# FSI6CAN.net
KiCad netlist of a schematic drawn in EAGLE
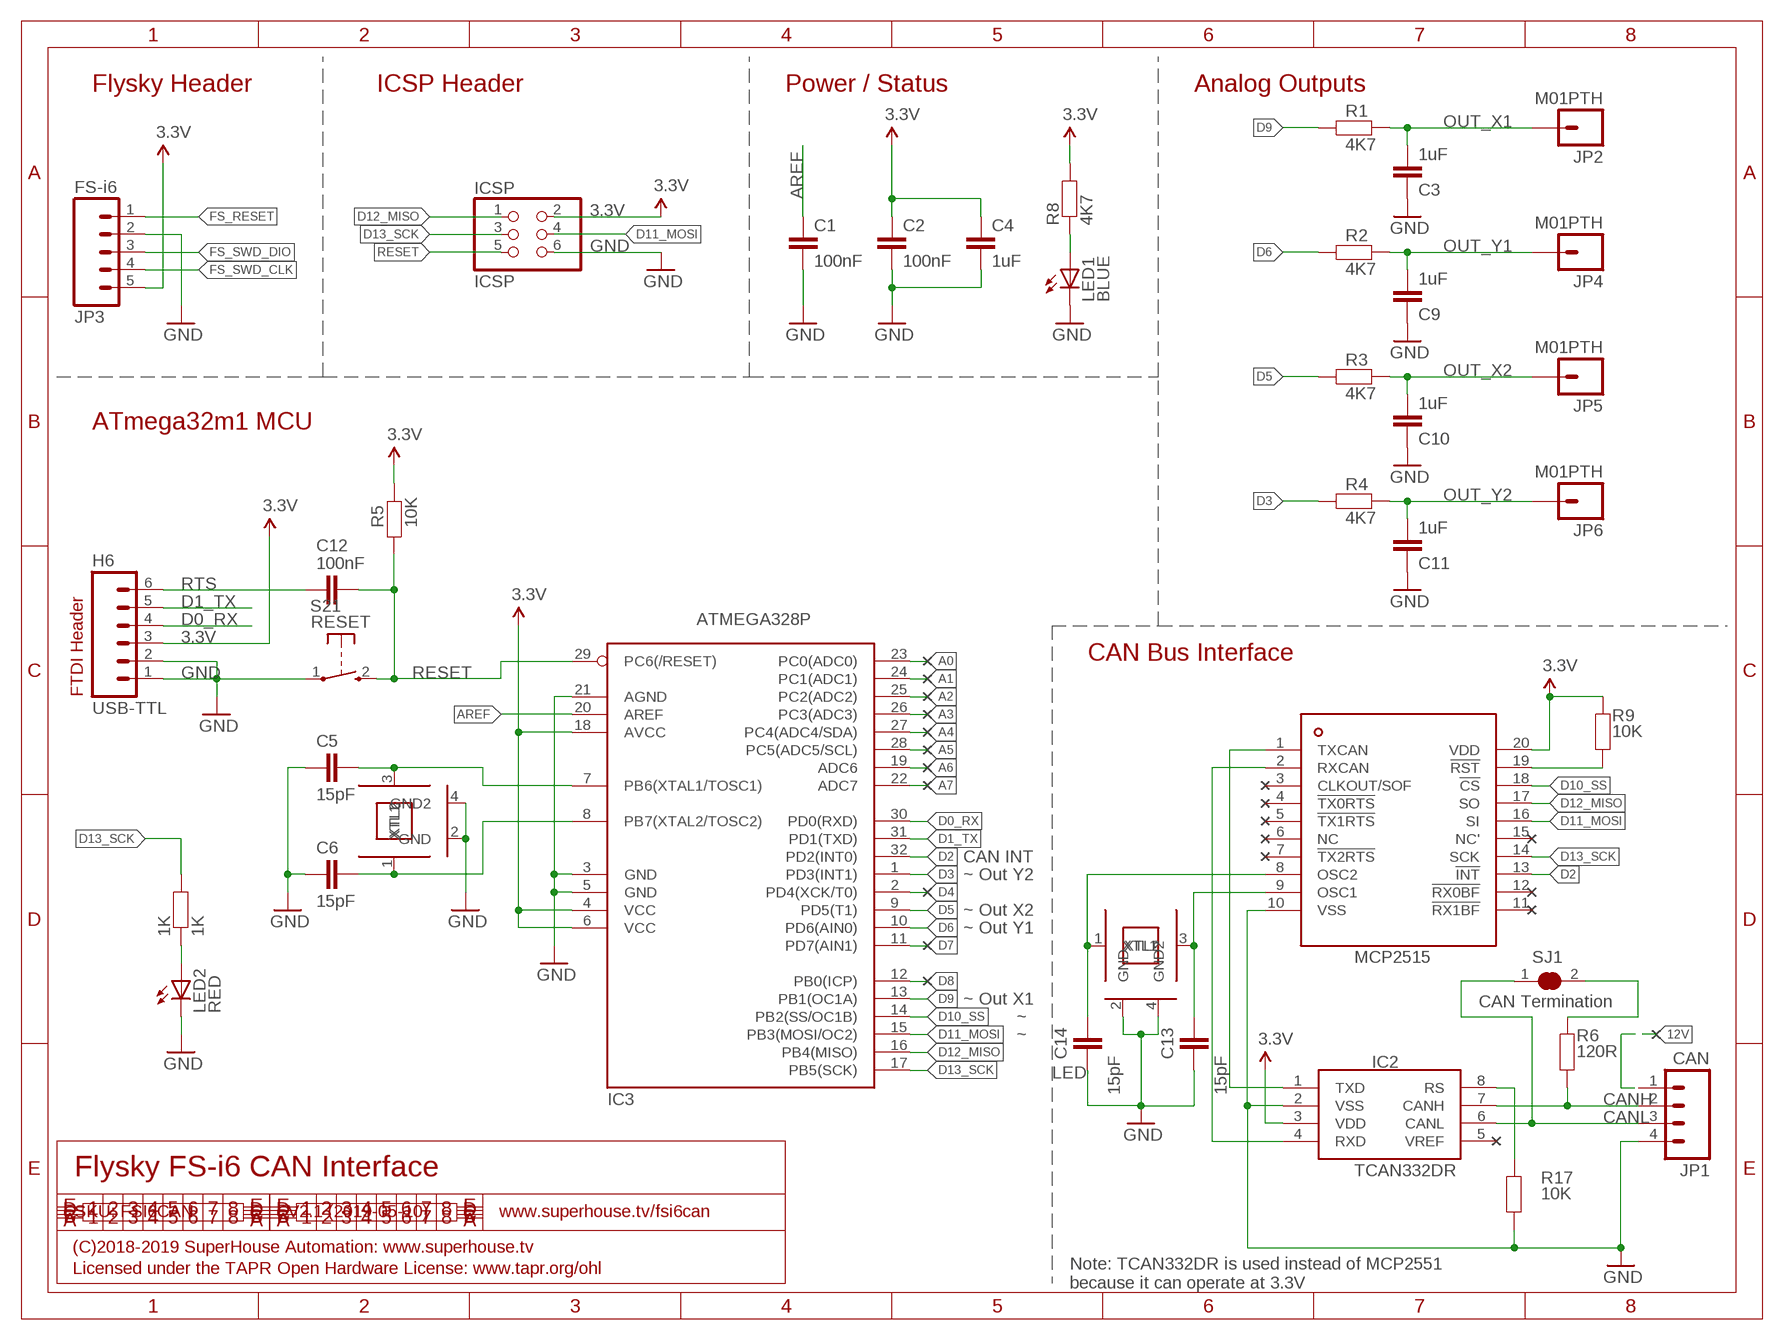
[diagram p0: schematic, sheet 1]

(export (version "E")
  (design (tool "Eeschema 10.0.6"))
  (components
    (comp (ref "1K")
      (value "1K")
      (footprint "eagle-import:R0603")
      (libsource (lib "eagle-import") (part "RESISTOR0603"))
    )
    (comp (ref "C1")
      (value "100nF")
      (footprint "eagle-import:C0603")
      (libsource (lib "eagle-import") (part "CAP0603"))
    )
    (comp (ref "C2")
      (value "100nF")
      (footprint "eagle-import:0603")
      (libsource (lib "eagle-import") (part "freetronics-master-v1.1_CAP0603"))
    )
    (comp (ref "C3")
      (value "1uF")
      (footprint "eagle-import:C0603")
      (libsource (lib "eagle-import") (part "CAP0603"))
    )
    (comp (ref "C4")
      (value "1uF")
      (footprint "eagle-import:0603")
      (libsource (lib "eagle-import") (part "freetronics-master-v1.1_CAP0603"))
    )
    (comp (ref "C5")
      (value "15pF")
      (footprint "eagle-import:C0603")
      (libsource (lib "eagle-import") (part "CAP0603"))
    )
    (comp (ref "C6")
      (value "15pF")
      (footprint "eagle-import:C0603")
      (libsource (lib "eagle-import") (part "CAP0603"))
    )
    (comp (ref "C9")
      (value "1uF")
      (footprint "eagle-import:C0603")
      (libsource (lib "eagle-import") (part "CAP0603"))
    )
    (comp (ref "C10")
      (value "1uF")
      (footprint "eagle-import:C0603")
      (libsource (lib "eagle-import") (part "CAP0603"))
    )
    (comp (ref "C11")
      (value "1uF")
      (footprint "eagle-import:C0603")
      (libsource (lib "eagle-import") (part "CAP0603"))
    )
    (comp (ref "C12")
      (value "100nF")
      (footprint "eagle-import:0603")
      (libsource (lib "eagle-import") (part "freetronics-master-v1.1_CAP0603"))
    )
    (comp (ref "C13")
      (value "15pF")
      (footprint "eagle-import:C0603")
      (libsource (lib "eagle-import") (part "CAP0603"))
    )
    (comp (ref "C14")
      (value "15pF")
      (footprint "eagle-import:C0603")
      (libsource (lib "eagle-import") (part "CAP0603"))
    )
    (comp (ref "H6")
      (value "USB-TTL")
      (footprint "eagle-import:1X06")
      (libsource (lib "eagle-import") (part "M06SIP"))
    )
    (comp (ref "IC2")
      (value "TCAN332DR")
      (footprint "eagle-import:SO08")
      (libsource (lib "eagle-import") (part "MCP2551"))
    )
    (comp (ref "IC3")
      (value "ATMEGA328P")
      (footprint "eagle-import:TQFP32-08")
      (libsource (lib "eagle-import") (part "AVR-MEGA8-AI"))
    )
    (comp (ref "IC4")
      (value "MCP2515")
      (footprint "eagle-import:TSSOP20")
      (libsource (lib "eagle-import") (part "MCP2515"))
    )
    (comp (ref "ICSP")
      (value "ICSP")
      (footprint "eagle-import:2X03")
      (libsource (lib "eagle-import") (part "PINHD-2X3"))
    )
    (comp (ref "JP1")
      (value "CAN")
      (footprint "eagle-import:1X04")
      (libsource (lib "eagle-import") (part "M04PTH"))
    )
    (comp (ref "JP2")
      (value "M01PTH")
      (footprint "eagle-import:1X01")
      (libsource (lib "eagle-import") (part "M01PTH"))
    )
    (comp (ref "JP3")
      (value "FS-i6")
      (footprint "eagle-import:1X05")
      (libsource (lib "eagle-import") (part "M05PTH"))
    )
    (comp (ref "JP4")
      (value "M01PTH")
      (footprint "eagle-import:1X01")
      (libsource (lib "eagle-import") (part "M01PTH"))
    )
    (comp (ref "JP5")
      (value "M01PTH")
      (footprint "eagle-import:1X01")
      (libsource (lib "eagle-import") (part "M01PTH"))
    )
    (comp (ref "JP6")
      (value "M01PTH")
      (footprint "eagle-import:1X01")
      (libsource (lib "eagle-import") (part "M01PTH"))
    )
    (comp (ref "LED1")
      (value "BLUE")
      (footprint "eagle-import:LED-0603")
      (libsource (lib "eagle-import") (part "LED0603"))
    )
    (comp (ref "LED2")
      (value "RED")
      (footprint "eagle-import:LED-0603")
      (libsource (lib "eagle-import") (part "LED0603"))
    )
    (comp (ref "R1")
      (value "4K7")
      (footprint "eagle-import:R0603")
      (libsource (lib "eagle-import") (part "RESISTOR0603"))
    )
    (comp (ref "R2")
      (value "4K7")
      (footprint "eagle-import:R0603")
      (libsource (lib "eagle-import") (part "RESISTOR0603"))
    )
    (comp (ref "R3")
      (value "4K7")
      (footprint "eagle-import:R0603")
      (libsource (lib "eagle-import") (part "RESISTOR0603"))
    )
    (comp (ref "R4")
      (value "4K7")
      (footprint "eagle-import:R0603")
      (libsource (lib "eagle-import") (part "RESISTOR0603"))
    )
    (comp (ref "R5")
      (value "10K")
      (footprint "eagle-import:0603")
      (libsource (lib "eagle-import") (part "freetronics-master-v1.1_RESISTOR0603"))
    )
    (comp (ref "R6")
      (value "120R")
      (footprint "eagle-import:0603")
      (libsource (lib "eagle-import") (part "freetronics-master-v1.1_RESISTOR0603"))
    )
    (comp (ref "R8")
      (value "4K7")
      (footprint "eagle-import:0603")
      (libsource (lib "eagle-import") (part "freetronics-jon_RESISTOR0603"))
    )
    (comp (ref "R9")
      (value "10K")
      (footprint "eagle-import:R0603")
      (libsource (lib "eagle-import") (part "RESISTOR0603"))
    )
    (comp (ref "R17")
      (value "10K")
      (footprint "eagle-import:R0603")
      (libsource (lib "eagle-import") (part "RESISTOR0603"))
    )
    (comp (ref "S21")
      (value "RESET")
      (footprint "eagle-import:TACTILE_SMT_3X4X2")
      (libsource (lib "eagle-import") (part "TAC_SWITCH_2PINSMT"))
    )
    (comp (ref "SJ1")
      (value "CAN Termination")
      (footprint "eagle-import:SJC")
      (libsource (lib "eagle-import") (part "SJCN"))
    )
    (comp (ref "XTL1")
      (value "8MHz")
      (footprint "eagle-import:CRYSTAL-SMD-3X2")
      (libsource (lib "eagle-import") (part "CRYSTAL-GND3X2"))
    )
    (comp (ref "XTL3")
      (value "16MHz")
      (footprint "eagle-import:CRYSTAL-SMD-3X2")
      (libsource (lib "eagle-import") (part "CRYSTAL-GND3X2"))
    )
  )
  (nets
    (net (code "1") (name "/CANH") (class "Default")
      (node (ref "IC2") (pin "7") (pinfunction "CANH_7") (pintype "bidirectional"))
      (node (ref "JP1") (pin "2") (pinfunction "2_2") (pintype "passive"))
      (node (ref "R6") (pin "1") (pinfunction "1_1") (pintype "passive"))
    )
    (net (code "2") (name "/CANL") (class "Default")
      (node (ref "IC2") (pin "6") (pinfunction "CANL_6") (pintype "bidirectional"))
      (node (ref "JP1") (pin "3") (pinfunction "3_3") (pintype "passive"))
      (node (ref "SJ1") (pin "1") (pinfunction "1_1") (pintype "passive"))
    )
    (net (code "3") (name "/OUT_X1") (class "Default")
      (node (ref "C3") (pin "1") (pinfunction "1_1") (pintype "passive"))
      (node (ref "JP2") (pin "1") (pinfunction "1_1") (pintype "passive"))
      (node (ref "R1") (pin "2") (pinfunction "2_2") (pintype "passive"))
    )
    (net (code "4") (name "/OUT_X2") (class "Default")
      (node (ref "C10") (pin "1") (pinfunction "1_1") (pintype "passive"))
      (node (ref "JP5") (pin "1") (pinfunction "1_1") (pintype "passive"))
      (node (ref "R3") (pin "2") (pinfunction "2_2") (pintype "passive"))
    )
    (net (code "5") (name "/OUT_Y1") (class "Default")
      (node (ref "C9") (pin "1") (pinfunction "1_1") (pintype "passive"))
      (node (ref "JP4") (pin "1") (pinfunction "1_1") (pintype "passive"))
      (node (ref "R2") (pin "2") (pinfunction "2_2") (pintype "passive"))
    )
    (net (code "6") (name "/OUT_Y2") (class "Default")
      (node (ref "C11") (pin "1") (pinfunction "1_1") (pintype "passive"))
      (node (ref "JP6") (pin "1") (pinfunction "1_1") (pintype "passive"))
      (node (ref "R4") (pin "2") (pinfunction "2_2") (pintype "passive"))
    )
    (net (code "7") (name "/RTS") (class "Default")
      (node (ref "C12") (pin "1") (pinfunction "1_1") (pintype "passive"))
      (node (ref "H6") (pin "6") (pinfunction "6_6") (pintype "passive"))
    )
    (net (code "8") (name "3.3V") (class "Default")
      (node (ref "C2") (pin "1") (pinfunction "1_1") (pintype "passive"))
      (node (ref "C4") (pin "1") (pinfunction "1_1") (pintype "passive"))
      (node (ref "H6") (pin "3") (pinfunction "3_3") (pintype "passive"))
      (node (ref "IC2") (pin "3") (pinfunction "VDD_3") (pintype "bidirectional"))
      (node (ref "IC3") (pin "18") (pinfunction "AVCC_18") (pintype "bidirectional"))
      (node (ref "IC3") (pin "4") (pinfunction "VCC_4") (pintype "bidirectional"))
      (node (ref "IC3") (pin "6") (pinfunction "VCC_6") (pintype "bidirectional"))
      (node (ref "IC4") (pin "20") (pinfunction "VDD_20") (pintype "bidirectional"))
      (node (ref "ICSP") (pin "2") (pinfunction "2_2") (pintype "passive"))
      (node (ref "JP3") (pin "5") (pinfunction "5_5") (pintype "passive"))
      (node (ref "R5") (pin "1") (pinfunction "1_1") (pintype "passive"))
      (node (ref "R8") (pin "2") (pinfunction "2_2") (pintype "passive"))
      (node (ref "R9") (pin "2") (pinfunction "2_2") (pintype "passive"))
    )
    (net (code "9") (name "12V") (class "Default")
      (node (ref "JP1") (pin "1") (pinfunction "1_1") (pintype "passive"))
    )
    (net (code "10") (name "A0") (class "Default")
      (node (ref "IC3") (pin "23") (pinfunction "PC0(ADC0)_23") (pintype "bidirectional"))
    )
    (net (code "11") (name "A1") (class "Default")
      (node (ref "IC3") (pin "24") (pinfunction "PC1(ADC1)_24") (pintype "bidirectional"))
    )
    (net (code "12") (name "A2") (class "Default")
      (node (ref "IC3") (pin "25") (pinfunction "PC2(ADC2)_25") (pintype "bidirectional"))
    )
    (net (code "13") (name "A3") (class "Default")
      (node (ref "IC3") (pin "26") (pinfunction "PC3(ADC3)_26") (pintype "bidirectional"))
    )
    (net (code "14") (name "A4") (class "Default")
      (node (ref "IC3") (pin "27") (pinfunction "PC4(ADC4/SDA)_27") (pintype "bidirectional"))
    )
    (net (code "15") (name "A5") (class "Default")
      (node (ref "IC3") (pin "28") (pinfunction "PC5(ADC5/SCL)_28") (pintype "bidirectional"))
    )
    (net (code "16") (name "A6") (class "Default")
      (node (ref "IC3") (pin "19") (pinfunction "ADC6_19") (pintype "bidirectional"))
    )
    (net (code "17") (name "A7") (class "Default")
      (node (ref "IC3") (pin "22") (pinfunction "ADC7_22") (pintype "bidirectional"))
    )
    (net (code "18") (name "AREF") (class "Default")
      (node (ref "C1") (pin "1") (pinfunction "1_1") (pintype "passive"))
      (node (ref "IC3") (pin "20") (pinfunction "AREF_20") (pintype "bidirectional"))
    )
    (net (code "19") (name "D0_RX") (class "Default")
      (node (ref "H6") (pin "4") (pinfunction "4_4") (pintype "passive"))
      (node (ref "IC3") (pin "30") (pinfunction "PD0(RXD)_30") (pintype "bidirectional"))
    )
    (net (code "20") (name "D1_TX") (class "Default")
      (node (ref "H6") (pin "5") (pinfunction "5_5") (pintype "passive"))
      (node (ref "IC3") (pin "31") (pinfunction "PD1(TXD)_31") (pintype "bidirectional"))
    )
    (net (code "21") (name "D2") (class "Default")
      (node (ref "IC3") (pin "32") (pinfunction "PD2(INT0)_32") (pintype "bidirectional"))
      (node (ref "IC4") (pin "13") (pinfunction "~{INT}_13") (pintype "bidirectional"))
    )
    (net (code "22") (name "D3") (class "Default")
      (node (ref "IC3") (pin "1") (pinfunction "PD3(INT1)_1") (pintype "bidirectional"))
      (node (ref "R4") (pin "1") (pinfunction "1_1") (pintype "passive"))
    )
    (net (code "23") (name "D4") (class "Default")
      (node (ref "IC3") (pin "2") (pinfunction "PD4(XCK/T0)_2") (pintype "bidirectional"))
    )
    (net (code "24") (name "D5") (class "Default")
      (node (ref "IC3") (pin "9") (pinfunction "PD5(T1)_9") (pintype "bidirectional"))
      (node (ref "R3") (pin "1") (pinfunction "1_1") (pintype "passive"))
    )
    (net (code "25") (name "D6") (class "Default")
      (node (ref "IC3") (pin "10") (pinfunction "PD6(AIN0)_10") (pintype "bidirectional"))
      (node (ref "R2") (pin "1") (pinfunction "1_1") (pintype "passive"))
    )
    (net (code "26") (name "D7") (class "Default")
      (node (ref "IC3") (pin "11") (pinfunction "PD7(AIN1)_11") (pintype "bidirectional"))
    )
    (net (code "27") (name "D8") (class "Default")
      (node (ref "IC3") (pin "12") (pinfunction "PB0(ICP)_12") (pintype "bidirectional"))
    )
    (net (code "28") (name "D9") (class "Default")
      (node (ref "IC3") (pin "13") (pinfunction "PB1(OC1A)_13") (pintype "bidirectional"))
      (node (ref "R1") (pin "1") (pinfunction "1_1") (pintype "passive"))
    )
    (net (code "29") (name "D10_SS") (class "Default")
      (node (ref "IC3") (pin "14") (pinfunction "PB2(SS/OC1B)_14") (pintype "bidirectional"))
      (node (ref "IC4") (pin "18") (pinfunction "~{CS}_18") (pintype "bidirectional"))
    )
    (net (code "30") (name "D11_MOSI") (class "Default")
      (node (ref "IC3") (pin "15") (pinfunction "PB3(MOSI/OC2)_15") (pintype "bidirectional"))
      (node (ref "IC4") (pin "16") (pinfunction "SI_16") (pintype "bidirectional"))
      (node (ref "ICSP") (pin "4") (pinfunction "4_4") (pintype "passive"))
    )
    (net (code "31") (name "D12_MISO") (class "Default")
      (node (ref "IC3") (pin "16") (pinfunction "PB4(MISO)_16") (pintype "bidirectional"))
      (node (ref "IC4") (pin "17") (pinfunction "SO_17") (pintype "bidirectional"))
      (node (ref "ICSP") (pin "1") (pinfunction "1_1") (pintype "passive"))
    )
    (net (code "32") (name "D13_SCK") (class "Default")
      (node (ref "1K") (pin "2") (pinfunction "2_2") (pintype "passive"))
      (node (ref "IC3") (pin "17") (pinfunction "PB5(SCK)_17") (pintype "bidirectional"))
      (node (ref "IC4") (pin "14") (pinfunction "SCK_14") (pintype "bidirectional"))
      (node (ref "ICSP") (pin "3") (pinfunction "3_3") (pintype "passive"))
    )
    (net (code "33") (name "FS_RESET") (class "Default")
      (node (ref "JP3") (pin "1") (pinfunction "1_1") (pintype "passive"))
    )
    (net (code "34") (name "FS_SWD_CLK") (class "Default")
      (node (ref "JP3") (pin "4") (pinfunction "4_4") (pintype "passive"))
    )
    (net (code "35") (name "FS_SWD_DIO") (class "Default")
      (node (ref "JP3") (pin "3") (pinfunction "3_3") (pintype "passive"))
    )
    (net (code "36") (name "GND") (class "Default")
      (node (ref "C1") (pin "2") (pinfunction "2_2") (pintype "passive"))
      (node (ref "C10") (pin "2") (pinfunction "2_2") (pintype "passive"))
      (node (ref "C11") (pin "2") (pinfunction "2_2") (pintype "passive"))
      (node (ref "C13") (pin "1") (pinfunction "1_1") (pintype "passive"))
      (node (ref "C14") (pin "1") (pinfunction "1_1") (pintype "passive"))
      (node (ref "C2") (pin "2") (pinfunction "2_2") (pintype "passive"))
      (node (ref "C3") (pin "2") (pinfunction "2_2") (pintype "passive"))
      (node (ref "C4") (pin "2") (pinfunction "2_2") (pintype "passive"))
      (node (ref "C5") (pin "1") (pinfunction "1_1") (pintype "passive"))
      (node (ref "C6") (pin "1") (pinfunction "1_1") (pintype "passive"))
      (node (ref "C9") (pin "2") (pinfunction "2_2") (pintype "passive"))
      (node (ref "H6") (pin "1") (pinfunction "1_1") (pintype "passive"))
      (node (ref "H6") (pin "2") (pinfunction "2_2") (pintype "passive"))
      (node (ref "IC2") (pin "2") (pinfunction "VSS_2") (pintype "bidirectional"))
      (node (ref "IC3") (pin "21") (pinfunction "AGND_21") (pintype "bidirectional"))
      (node (ref "IC3") (pin "3") (pinfunction "GND_3") (pintype "bidirectional"))
      (node (ref "IC3") (pin "5") (pinfunction "GND_5") (pintype "bidirectional"))
      (node (ref "IC4") (pin "10") (pinfunction "VSS_10") (pintype "bidirectional"))
      (node (ref "ICSP") (pin "6") (pinfunction "6_6") (pintype "passive"))
      (node (ref "JP1") (pin "4") (pinfunction "4_4") (pintype "passive"))
      (node (ref "JP3") (pin "2") (pinfunction "2_2") (pintype "passive"))
      (node (ref "LED1") (pin "C") (pinfunction "C_C") (pintype "passive"))
      (node (ref "LED2") (pin "C") (pinfunction "C_C") (pintype "passive"))
      (node (ref "R17") (pin "1") (pinfunction "1_1") (pintype "passive"))
      (node (ref "S21") (pin "1") (pinfunction "P_1") (pintype "passive"))
      (node (ref "XTL1") (pin "2") (pinfunction "GND_2") (pintype "bidirectional"))
      (node (ref "XTL1") (pin "4") (pinfunction "GND2_4") (pintype "bidirectional"))
      (node (ref "XTL3") (pin "2") (pinfunction "GND_2") (pintype "bidirectional"))
      (node (ref "XTL3") (pin "4") (pinfunction "GND2_4") (pintype "bidirectional"))
    )
    (net (code "37") (name "Net-(1K-Pad1)") (class "Default")
      (node (ref "1K") (pin "1") (pinfunction "1_1") (pintype "passive"))
      (node (ref "LED2") (pin "A") (pinfunction "A_A") (pintype "passive"))
    )
    (net (code "38") (name "Net-(IC2-RS)") (class "Default")
      (node (ref "IC2") (pin "8") (pinfunction "RS_8") (pintype "bidirectional"))
      (node (ref "R17") (pin "2") (pinfunction "2_2") (pintype "passive"))
    )
    (net (code "39") (name "Net-(IC2-RXD)") (class "Default")
      (node (ref "IC2") (pin "4") (pinfunction "RXD_4") (pintype "bidirectional"))
      (node (ref "IC4") (pin "2") (pinfunction "RXCAN_2") (pintype "bidirectional"))
    )
    (net (code "40") (name "Net-(IC2-TXD)") (class "Default")
      (node (ref "IC2") (pin "1") (pinfunction "TXD_1") (pintype "bidirectional"))
      (node (ref "IC4") (pin "1") (pinfunction "TXCAN_1") (pintype "bidirectional"))
    )
    (net (code "41") (name "Net-(IC3-PB6(XTAL1{slash}TOSC1))") (class "Default")
      (node (ref "C5") (pin "2") (pinfunction "2_2") (pintype "passive"))
      (node (ref "IC3") (pin "7") (pinfunction "PB6(XTAL1/TOSC1)_7") (pintype "bidirectional"))
      (node (ref "XTL1") (pin "3") (pinfunction "XTL2_3") (pintype "bidirectional"))
    )
    (net (code "42") (name "Net-(IC3-PB7(XTAL2{slash}TOSC2))") (class "Default")
      (node (ref "C6") (pin "2") (pinfunction "2_2") (pintype "passive"))
      (node (ref "IC3") (pin "8") (pinfunction "PB7(XTAL2/TOSC2)_8") (pintype "bidirectional"))
      (node (ref "XTL1") (pin "1") (pinfunction "XTL1_1") (pintype "bidirectional"))
    )
    (net (code "43") (name "Net-(IC4-OSC1)") (class "Default")
      (node (ref "C13") (pin "2") (pinfunction "2_2") (pintype "passive"))
      (node (ref "IC4") (pin "9") (pinfunction "OSC1_9") (pintype "bidirectional"))
      (node (ref "XTL3") (pin "3") (pinfunction "XTL2_3") (pintype "bidirectional"))
    )
    (net (code "44") (name "Net-(IC4-OSC2)") (class "Default")
      (node (ref "C14") (pin "2") (pinfunction "2_2") (pintype "passive"))
      (node (ref "IC4") (pin "8") (pinfunction "OSC2_8") (pintype "bidirectional"))
      (node (ref "XTL3") (pin "1") (pinfunction "XTL1_1") (pintype "bidirectional"))
    )
    (net (code "45") (name "Net-(IC4-~{RST})") (class "Default")
      (node (ref "IC4") (pin "19") (pinfunction "~{RST}_19") (pintype "bidirectional"))
      (node (ref "R9") (pin "1") (pinfunction "1_1") (pintype "passive"))
    )
    (net (code "46") (name "Net-(LED1-PadA)") (class "Default")
      (node (ref "LED1") (pin "A") (pinfunction "A_A") (pintype "passive"))
      (node (ref "R8") (pin "1") (pinfunction "1_1") (pintype "passive"))
    )
    (net (code "47") (name "Net-(R6-Pad2)") (class "Default")
      (node (ref "R6") (pin "2") (pinfunction "2_2") (pintype "passive"))
      (node (ref "SJ1") (pin "2") (pinfunction "2_2") (pintype "passive"))
    )
    (net (code "48") (name "RESET") (class "Default")
      (node (ref "C12") (pin "2") (pinfunction "2_2") (pintype "passive"))
      (node (ref "IC3") (pin "29") (pinfunction "PC6(/RESET)_29") (pintype "bidirectional"))
      (node (ref "ICSP") (pin "5") (pinfunction "5_5") (pintype "passive"))
      (node (ref "R5") (pin "2") (pinfunction "2_2") (pintype "passive"))
      (node (ref "S21") (pin "2") (pinfunction "S_2") (pintype "passive"))
    )
    (net (code "49") (name "unconnected-(IC2-VREF-Pad5)") (class "Default")
      (node (ref "IC2") (pin "5") (pinfunction "VREF_5") (pintype "bidirectional"))
    )
    (net (code "50") (name "unconnected-(IC4-CLKOUT{slash}SOF-Pad3)") (class "Default")
      (node (ref "IC4") (pin "3") (pinfunction "CLKOUT/SOF_3") (pintype "bidirectional"))
    )
    (net (code "51") (name "unconnected-(IC4-NC'-Pad15)") (class "Default")
      (node (ref "IC4") (pin "15") (pinfunction "NC'_15") (pintype "bidirectional"))
    )
    (net (code "52") (name "unconnected-(IC4-NC-Pad6)") (class "Default")
      (node (ref "IC4") (pin "6") (pinfunction "NC_6") (pintype "bidirectional"))
    )
    (net (code "53") (name "unconnected-(IC4-~{RX0BF}-Pad12)") (class "Default")
      (node (ref "IC4") (pin "12") (pinfunction "~{RX0BF}_12") (pintype "bidirectional"))
    )
    (net (code "54") (name "unconnected-(IC4-~{RX1BF}-Pad11)") (class "Default")
      (node (ref "IC4") (pin "11") (pinfunction "~{RX1BF}_11") (pintype "bidirectional"))
    )
    (net (code "55") (name "unconnected-(IC4-~{TX0RTS}-Pad4)") (class "Default")
      (node (ref "IC4") (pin "4") (pinfunction "~{TX0RTS}_4") (pintype "bidirectional"))
    )
    (net (code "56") (name "unconnected-(IC4-~{TX1RTS}-Pad5)") (class "Default")
      (node (ref "IC4") (pin "5") (pinfunction "~{TX1RTS}_5") (pintype "bidirectional"))
    )
    (net (code "57") (name "unconnected-(IC4-~{TX2RTS}-Pad7)") (class "Default")
      (node (ref "IC4") (pin "7") (pinfunction "~{TX2RTS}_7") (pintype "bidirectional"))
    )
  )
)
